# Light_V1_0.net
KiCad netlist of a schematic drawn in EAGLE
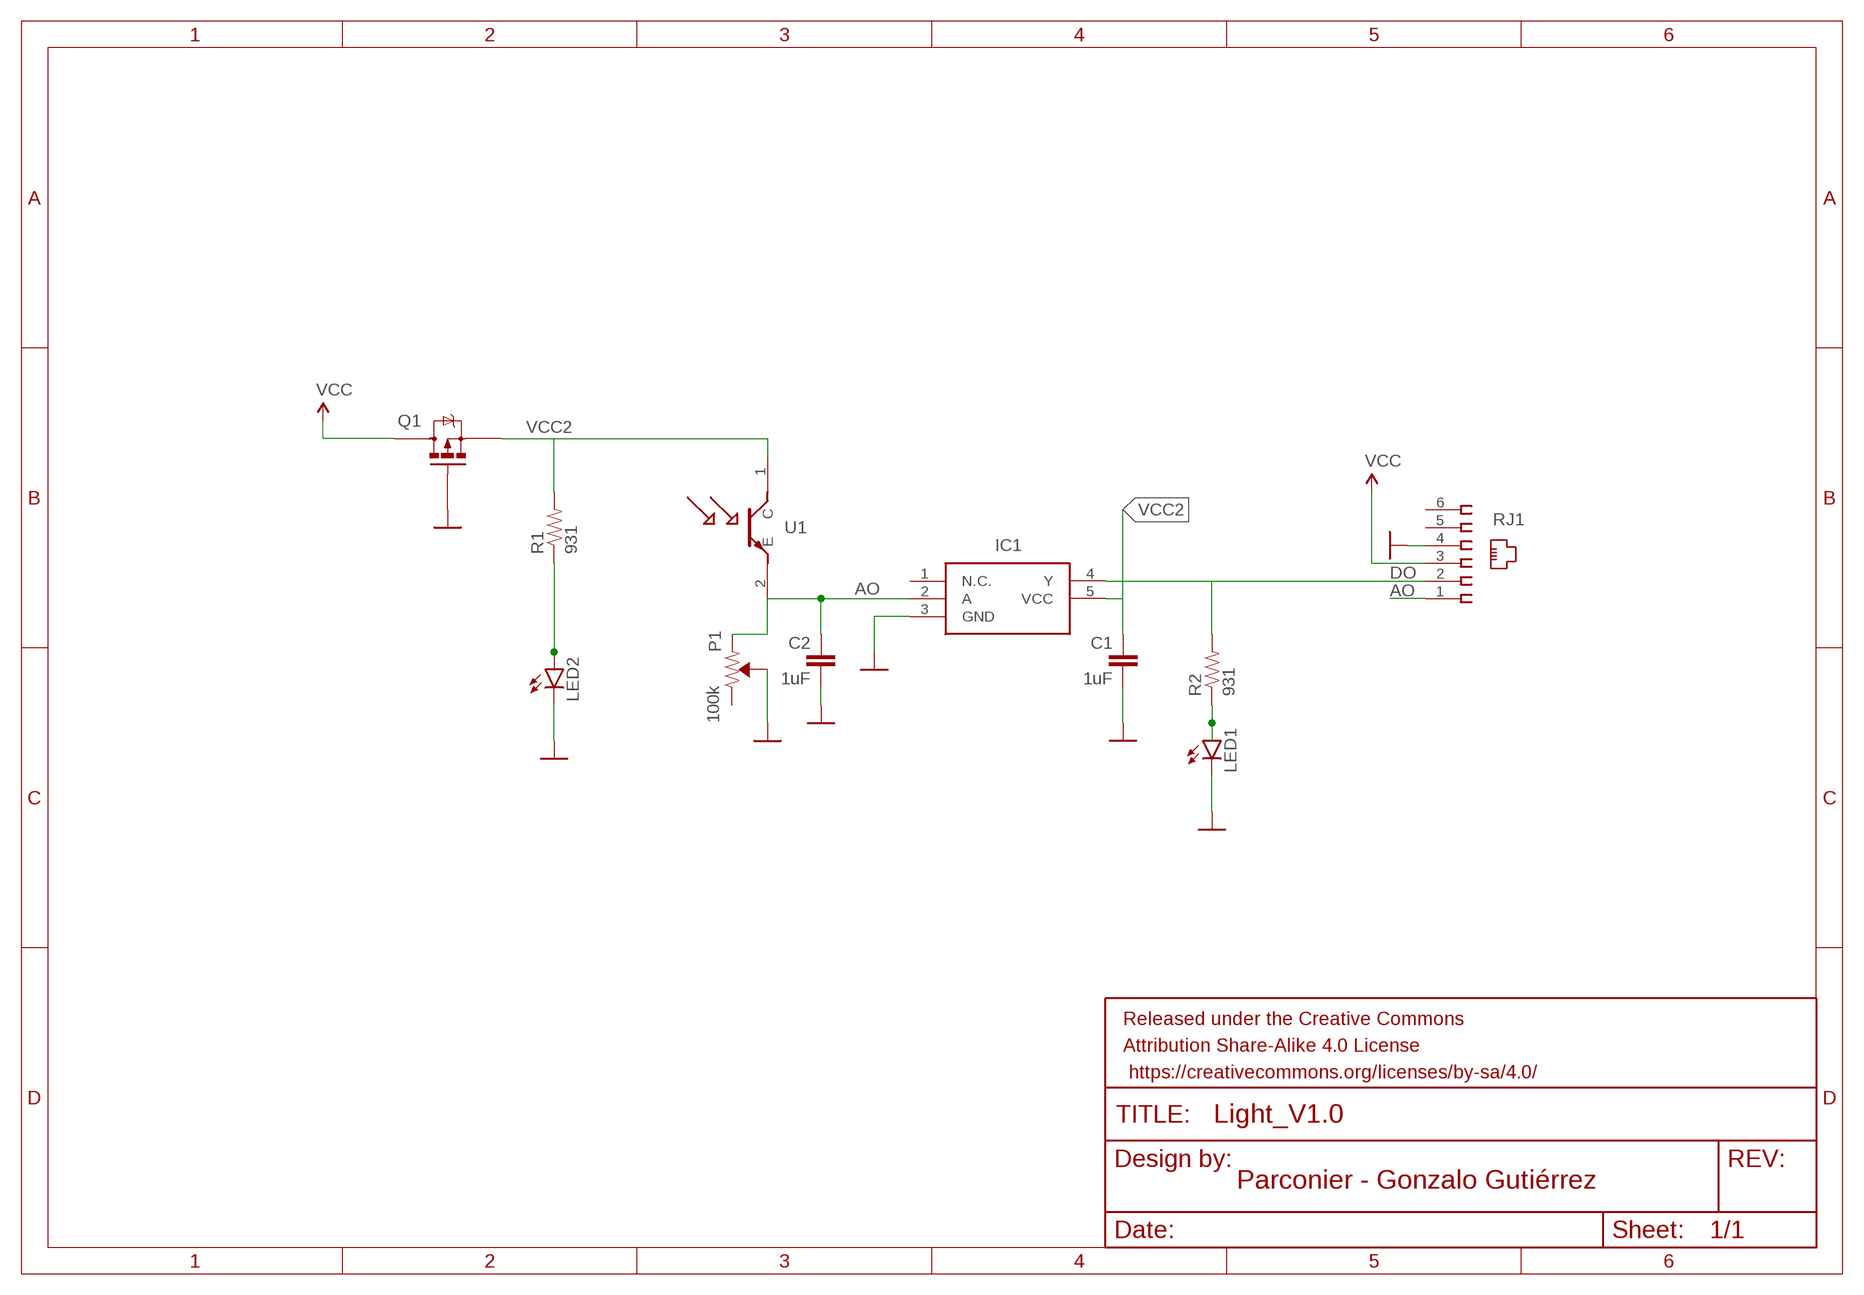
[diagram p0: schematic, sheet 1]

(export (version "E")
  (design (tool "Eeschema 10.0.6"))
  (components
    (comp (ref "C1")
      (value "1uF")
      (footprint "eagle-import:0402")
      (fields (field (name "MPN") "CC0402ZRY5V6BB105"))
      (libsource (lib "eagle-import") (part "CAP_0402"))
    )
    (comp (ref "C2")
      (value "1uF")
      (footprint "eagle-import:0402")
      (fields (field (name "MPN") "CC0402ZRY5V6BB105"))
      (libsource (lib "eagle-import") (part "CAP_0402"))
    )
    (comp (ref "IC1")
      (value "74LVC1G14GW-Q100,1")
      (footprint "eagle-import:SOT65P212X110-5N")
      (fields (field (name "RS_PART_NUMBER") "1526474") (field (name "MPN") "74AHC1G14GW-Q100,1"))
      (libsource (lib "eagle-import") (part "74LVC1G14GW-Q100,1"))
    )
    (comp (ref "LED1")
      (value "LED0603")
      (footprint "eagle-import:LED-0603")
      (fields (field (name "MPN") "LB Q39E-L2OO-35-1"))
      (libsource (lib "eagle-import") (part "LED0603"))
    )
    (comp (ref "LED2")
      (value "LED0603")
      (footprint "eagle-import:LED-0603")
      (fields (field (name "MPN") "LTST-C193KRKT-5A "))
      (libsource (lib "eagle-import") (part "LED0603"))
    )
    (comp (ref "P1")
      (value "100k")
      (footprint "eagle-import:3309W-1-104")
      (fields (field (name "MPN") "3309W-1-104"))
      (libsource (lib "eagle-import") (part "TRIMPOT"))
    )
    (comp (ref "Q1")
      (value "RU1C002ZPTCL")
      (footprint "eagle-import:SOTFL65P210X105-3N")
      (fields (field (name "SPICEPREFIX") "Q"))
      (libsource (lib "eagle-import") (part "RU1C002ZPTCL"))
    )
    (comp (ref "R1")
      (value "931")
      (footprint "eagle-import:RESC1005X35")
      (fields (field (name "MPN") "RC0402FR-07931RL"))
      (libsource (lib "eagle-import") (part "RES_0402"))
    )
    (comp (ref "R2")
      (value "931")
      (footprint "eagle-import:RESC1005X35")
      (fields (field (name "MPN") "RC0402FR-07931RL"))
      (libsource (lib "eagle-import") (part "RES_0402"))
    )
    (comp (ref "RJ1")
      (value "615006138421")
      (footprint "eagle-import:615006138421")
      (fields (field (name "RS_PART_NUMBER") "7350282") (field (name "MPN") "54601-906WPLF"))
      (libsource (lib "eagle-import") (part "615006138421"))
    )
    (comp (ref "U1")
      (value "NJL7302L-F3")
      (footprint "eagle-import:NJL7302L-F3")
      (libsource (lib "eagle-import") (part "NJL7302L-F3"))
    )
  )
  (nets
    (net (code "1") (name "/AO") (class "Default")
      (node (ref "C2") (pin "1") (pinfunction "1_1") (pintype "passive"))
      (node (ref "IC1") (pin "2") (pinfunction "A_2") (pintype "bidirectional"))
      (node (ref "P1") (pin "1") (pinfunction "CCW_1") (pintype "passive"))
      (node (ref "RJ1") (pin "1") (pinfunction "1_1") (pintype "input"))
      (node (ref "U1") (pin "2") (pinfunction "E_2") (pintype "bidirectional"))
    )
    (net (code "2") (name "/DO") (class "Default")
      (node (ref "IC1") (pin "4") (pinfunction "Y_4") (pintype "bidirectional"))
      (node (ref "R2") (pin "2") (pinfunction "2_2") (pintype "passive"))
      (node (ref "RJ1") (pin "2") (pinfunction "2_2") (pintype "input"))
    )
    (net (code "3") (name "GND") (class "Default")
      (node (ref "C1") (pin "2") (pinfunction "2_2") (pintype "passive"))
      (node (ref "C2") (pin "2") (pinfunction "2_2") (pintype "passive"))
      (node (ref "IC1") (pin "3") (pinfunction "GND_3") (pintype "bidirectional"))
      (node (ref "LED1") (pin "C") (pinfunction "C_C") (pintype "passive"))
      (node (ref "LED2") (pin "C") (pinfunction "C_C") (pintype "passive"))
      (node (ref "P1") (pin "2") (pinfunction "WIPER_2") (pintype "passive"))
      (node (ref "Q1") (pin "1") (pinfunction "G_1") (pintype "bidirectional"))
      (node (ref "RJ1") (pin "4") (pinfunction "4_4") (pintype "input"))
    )
    (net (code "4") (name "Net-(LED1-PadA)") (class "Default")
      (node (ref "LED1") (pin "A") (pinfunction "A_A") (pintype "passive"))
      (node (ref "R2") (pin "1") (pinfunction "1_1") (pintype "passive"))
    )
    (net (code "5") (name "Net-(LED2-PadA)") (class "Default")
      (node (ref "LED2") (pin "A") (pinfunction "A_A") (pintype "passive"))
      (node (ref "R1") (pin "1") (pinfunction "1_1") (pintype "passive"))
    )
    (net (code "6") (name "VCC") (class "Default")
      (node (ref "Q1") (pin "3") (pinfunction "D_3") (pintype "bidirectional"))
      (node (ref "RJ1") (pin "3") (pinfunction "3_3") (pintype "input"))
    )
    (net (code "7") (name "VCC2") (class "Default")
      (node (ref "C1") (pin "1") (pinfunction "1_1") (pintype "passive"))
      (node (ref "IC1") (pin "5") (pinfunction "VCC_5") (pintype "bidirectional"))
      (node (ref "Q1") (pin "2") (pinfunction "S_2") (pintype "bidirectional"))
      (node (ref "R1") (pin "2") (pinfunction "2_2") (pintype "passive"))
      (node (ref "U1") (pin "1") (pinfunction "C_1") (pintype "bidirectional"))
    )
    (net (code "8") (name "unconnected-(IC1-N.C.-Pad1)") (class "Default")
      (node (ref "IC1") (pin "1") (pinfunction "N.C._1") (pintype "no_connect"))
    )
    (net (code "9") (name "unconnected-(P1-CW-Pad3)") (class "Default")
      (node (ref "P1") (pin "3") (pinfunction "CW_3") (pintype "passive"))
    )
    (net (code "10") (name "unconnected-(RJ1-Pad5)") (class "Default")
      (node (ref "RJ1") (pin "5") (pinfunction "5_5") (pintype "input"))
    )
    (net (code "11") (name "unconnected-(RJ1-Pad6)") (class "Default")
      (node (ref "RJ1") (pin "6") (pinfunction "6_6") (pintype "input"))
    )
  )
)
